# dual_vca_pnl.net
KiCad netlist of a schematic drawn in EAGLE
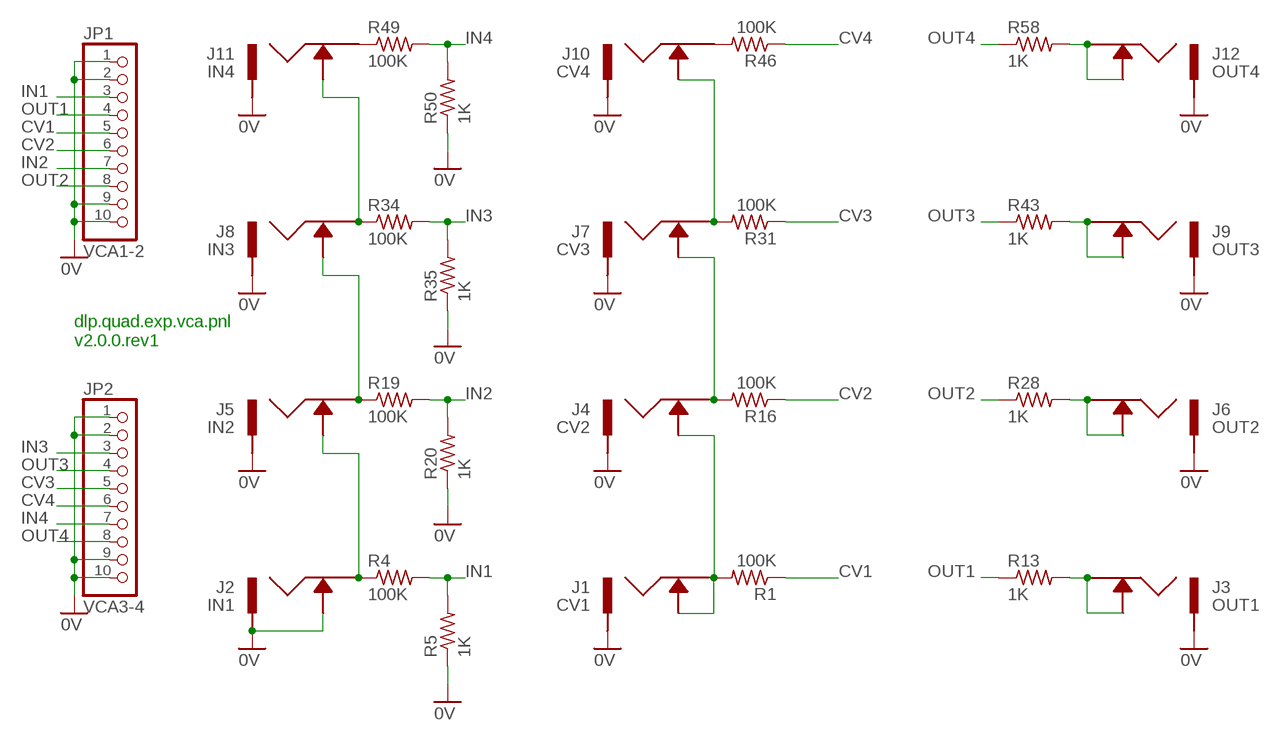
[diagram p0: schematic, sheet 1]

(export (version "E")
  (design (tool "Eeschema 10.0.6"))
  (components
    (comp (ref "J1")
      (value "CV1")
      (footprint "eagle-import:ACJM-MV35-2S")
      (libsource (lib "eagle-import") (part "ACJM-MV35-2S"))
    )
    (comp (ref "J2")
      (value "IN1")
      (footprint "eagle-import:ACJM-MV35-2S")
      (libsource (lib "eagle-import") (part "ACJM-MV35-2S"))
    )
    (comp (ref "J3")
      (value "OUT1")
      (footprint "eagle-import:ACJM-MV35-2S")
      (libsource (lib "eagle-import") (part "ACJM-MV35-2S"))
    )
    (comp (ref "J4")
      (value "CV2")
      (footprint "eagle-import:ACJM-MV35-2S")
      (libsource (lib "eagle-import") (part "ACJM-MV35-2S"))
    )
    (comp (ref "J5")
      (value "IN2")
      (footprint "eagle-import:ACJM-MV35-2S")
      (libsource (lib "eagle-import") (part "ACJM-MV35-2S"))
    )
    (comp (ref "J6")
      (value "OUT2")
      (footprint "eagle-import:ACJM-MV35-2S")
      (libsource (lib "eagle-import") (part "ACJM-MV35-2S"))
    )
    (comp (ref "J7")
      (value "CV3")
      (footprint "eagle-import:ACJM-MV35-2S")
      (libsource (lib "eagle-import") (part "ACJM-MV35-2S"))
    )
    (comp (ref "J8")
      (value "IN3")
      (footprint "eagle-import:ACJM-MV35-2S")
      (libsource (lib "eagle-import") (part "ACJM-MV35-2S"))
    )
    (comp (ref "J9")
      (value "OUT3")
      (footprint "eagle-import:ACJM-MV35-2S")
      (libsource (lib "eagle-import") (part "ACJM-MV35-2S"))
    )
    (comp (ref "J10")
      (value "CV4")
      (footprint "eagle-import:ACJM-MV35-2S")
      (libsource (lib "eagle-import") (part "ACJM-MV35-2S"))
    )
    (comp (ref "J11")
      (value "IN4")
      (footprint "eagle-import:ACJM-MV35-2S")
      (libsource (lib "eagle-import") (part "ACJM-MV35-2S"))
    )
    (comp (ref "J12")
      (value "OUT4")
      (footprint "eagle-import:ACJM-MV35-2S")
      (libsource (lib "eagle-import") (part "ACJM-MV35-2S"))
    )
    (comp (ref "JP1")
      (value "VCA1-2")
      (footprint "eagle-import:1X10")
      (libsource (lib "eagle-import") (part "PINHD-1X10"))
    )
    (comp (ref "JP2")
      (value "VCA3-4")
      (footprint "eagle-import:1X10")
      (libsource (lib "eagle-import") (part "PINHD-1X10"))
    )
    (comp (ref "R1")
      (value "100K")
      (footprint "eagle-import:0207_7")
      (libsource (lib "eagle-import") (part "R-US_0207/7"))
    )
    (comp (ref "R4")
      (value "100K")
      (footprint "eagle-import:0207_7")
      (libsource (lib "eagle-import") (part "R-US_0207/7"))
    )
    (comp (ref "R5")
      (value "1K")
      (footprint "eagle-import:0207_7")
      (libsource (lib "eagle-import") (part "R-US_0207/7"))
    )
    (comp (ref "R13")
      (value "1K")
      (footprint "eagle-import:0207_7")
      (libsource (lib "eagle-import") (part "R-US_0207/7"))
    )
    (comp (ref "R16")
      (value "100K")
      (footprint "eagle-import:0207_7")
      (libsource (lib "eagle-import") (part "R-US_0207/7"))
    )
    (comp (ref "R19")
      (value "100K")
      (footprint "eagle-import:0207_7")
      (libsource (lib "eagle-import") (part "R-US_0207/7"))
    )
    (comp (ref "R20")
      (value "1K")
      (footprint "eagle-import:0207_7")
      (libsource (lib "eagle-import") (part "R-US_0207/7"))
    )
    (comp (ref "R28")
      (value "1K")
      (footprint "eagle-import:0207_7")
      (libsource (lib "eagle-import") (part "R-US_0207/7"))
    )
    (comp (ref "R31")
      (value "100K")
      (footprint "eagle-import:0207_7")
      (libsource (lib "eagle-import") (part "R-US_0207/7"))
    )
    (comp (ref "R34")
      (value "100K")
      (footprint "eagle-import:0207_7")
      (libsource (lib "eagle-import") (part "R-US_0207/7"))
    )
    (comp (ref "R35")
      (value "1K")
      (footprint "eagle-import:0207_7")
      (libsource (lib "eagle-import") (part "R-US_0207/7"))
    )
    (comp (ref "R43")
      (value "1K")
      (footprint "eagle-import:0207_7")
      (libsource (lib "eagle-import") (part "R-US_0207/7"))
    )
    (comp (ref "R46")
      (value "100K")
      (footprint "eagle-import:0207_7")
      (libsource (lib "eagle-import") (part "R-US_0207/7"))
    )
    (comp (ref "R49")
      (value "100K")
      (footprint "eagle-import:0207_7")
      (libsource (lib "eagle-import") (part "R-US_0207/7"))
    )
    (comp (ref "R50")
      (value "1K")
      (footprint "eagle-import:0207_7")
      (libsource (lib "eagle-import") (part "R-US_0207/7"))
    )
    (comp (ref "R58")
      (value "1K")
      (footprint "eagle-import:0207_7")
      (libsource (lib "eagle-import") (part "R-US_0207/7"))
    )
  )
  (nets
    (net (code "1") (name "/CV1") (class "Default")
      (node (ref "JP1") (pin "5") (pinfunction "5_5") (pintype "passive"))
      (node (ref "R1") (pin "1") (pinfunction "1_1") (pintype "passive"))
    )
    (net (code "2") (name "/CV2") (class "Default")
      (node (ref "JP1") (pin "6") (pinfunction "6_6") (pintype "passive"))
      (node (ref "R16") (pin "1") (pinfunction "1_1") (pintype "passive"))
    )
    (net (code "3") (name "/CV3") (class "Default")
      (node (ref "JP2") (pin "5") (pinfunction "5_5") (pintype "passive"))
      (node (ref "R31") (pin "1") (pinfunction "1_1") (pintype "passive"))
    )
    (net (code "4") (name "/CV4") (class "Default")
      (node (ref "JP2") (pin "6") (pinfunction "6_6") (pintype "passive"))
      (node (ref "R46") (pin "1") (pinfunction "1_1") (pintype "passive"))
    )
    (net (code "5") (name "/IN1") (class "Default")
      (node (ref "JP1") (pin "3") (pinfunction "3_3") (pintype "passive"))
      (node (ref "R4") (pin "2") (pinfunction "2_2") (pintype "passive"))
      (node (ref "R5") (pin "2") (pinfunction "2_2") (pintype "passive"))
    )
    (net (code "6") (name "/IN2") (class "Default")
      (node (ref "JP1") (pin "7") (pinfunction "7_7") (pintype "passive"))
      (node (ref "R19") (pin "2") (pinfunction "2_2") (pintype "passive"))
      (node (ref "R20") (pin "2") (pinfunction "2_2") (pintype "passive"))
    )
    (net (code "7") (name "/IN3") (class "Default")
      (node (ref "JP2") (pin "3") (pinfunction "3_3") (pintype "passive"))
      (node (ref "R34") (pin "2") (pinfunction "2_2") (pintype "passive"))
      (node (ref "R35") (pin "2") (pinfunction "2_2") (pintype "passive"))
    )
    (net (code "8") (name "/IN4") (class "Default")
      (node (ref "JP2") (pin "7") (pinfunction "7_7") (pintype "passive"))
      (node (ref "R49") (pin "2") (pinfunction "2_2") (pintype "passive"))
      (node (ref "R50") (pin "2") (pinfunction "2_2") (pintype "passive"))
    )
    (net (code "9") (name "/OUT1") (class "Default")
      (node (ref "JP1") (pin "4") (pinfunction "4_4") (pintype "passive"))
      (node (ref "R13") (pin "1") (pinfunction "1_1") (pintype "passive"))
    )
    (net (code "10") (name "/OUT2") (class "Default")
      (node (ref "JP1") (pin "8") (pinfunction "8_8") (pintype "passive"))
      (node (ref "R28") (pin "1") (pinfunction "1_1") (pintype "passive"))
    )
    (net (code "11") (name "/OUT3") (class "Default")
      (node (ref "JP2") (pin "4") (pinfunction "4_4") (pintype "passive"))
      (node (ref "R43") (pin "1") (pinfunction "1_1") (pintype "passive"))
    )
    (net (code "12") (name "/OUT4") (class "Default")
      (node (ref "JP2") (pin "8") (pinfunction "8_8") (pintype "passive"))
      (node (ref "R58") (pin "1") (pinfunction "1_1") (pintype "passive"))
    )
    (net (code "13") (name "0V") (class "Default")
      (node (ref "J1") (pin "P$1") (pinfunction "P$1_P$1") (pintype "bidirectional"))
      (node (ref "J10") (pin "P$1") (pinfunction "P$1_P$1") (pintype "bidirectional"))
      (node (ref "J11") (pin "P$1") (pinfunction "P$1_P$1") (pintype "bidirectional"))
      (node (ref "J12") (pin "P$1") (pinfunction "P$1_P$1") (pintype "bidirectional"))
      (node (ref "J2") (pin "P$1") (pinfunction "P$1_P$1") (pintype "bidirectional"))
      (node (ref "J2") (pin "P$2") (pinfunction "P$3_P$2") (pintype "bidirectional"))
      (node (ref "J3") (pin "P$1") (pinfunction "P$1_P$1") (pintype "bidirectional"))
      (node (ref "J4") (pin "P$1") (pinfunction "P$1_P$1") (pintype "bidirectional"))
      (node (ref "J5") (pin "P$1") (pinfunction "P$1_P$1") (pintype "bidirectional"))
      (node (ref "J6") (pin "P$1") (pinfunction "P$1_P$1") (pintype "bidirectional"))
      (node (ref "J7") (pin "P$1") (pinfunction "P$1_P$1") (pintype "bidirectional"))
      (node (ref "J8") (pin "P$1") (pinfunction "P$1_P$1") (pintype "bidirectional"))
      (node (ref "J9") (pin "P$1") (pinfunction "P$1_P$1") (pintype "bidirectional"))
      (node (ref "JP1") (pin "1") (pinfunction "1_1") (pintype "passive"))
      (node (ref "JP1") (pin "10") (pinfunction "10_10") (pintype "passive"))
      (node (ref "JP1") (pin "2") (pinfunction "2_2") (pintype "passive"))
      (node (ref "JP1") (pin "9") (pinfunction "9_9") (pintype "passive"))
      (node (ref "JP2") (pin "1") (pinfunction "1_1") (pintype "passive"))
      (node (ref "JP2") (pin "10") (pinfunction "10_10") (pintype "passive"))
      (node (ref "JP2") (pin "2") (pinfunction "2_2") (pintype "passive"))
      (node (ref "JP2") (pin "9") (pinfunction "9_9") (pintype "passive"))
      (node (ref "R20") (pin "1") (pinfunction "1_1") (pintype "passive"))
      (node (ref "R35") (pin "1") (pinfunction "1_1") (pintype "passive"))
      (node (ref "R5") (pin "1") (pinfunction "1_1") (pintype "passive"))
      (node (ref "R50") (pin "1") (pinfunction "1_1") (pintype "passive"))
    )
    (net (code "14") (name "Net-(J1-P$2)") (class "Default")
      (node (ref "J1") (pin "P$2") (pinfunction "P$3_P$2") (pintype "bidirectional"))
      (node (ref "J1") (pin "P$3") (pinfunction "P$2_P$3") (pintype "bidirectional"))
      (node (ref "J4") (pin "P$2") (pinfunction "P$3_P$2") (pintype "bidirectional"))
      (node (ref "R1") (pin "2") (pinfunction "2_2") (pintype "passive"))
    )
    (net (code "15") (name "Net-(J2-P$2)") (class "Default")
      (node (ref "J2") (pin "P$3") (pinfunction "P$2_P$3") (pintype "bidirectional"))
      (node (ref "J5") (pin "P$2") (pinfunction "P$3_P$2") (pintype "bidirectional"))
      (node (ref "R4") (pin "1") (pinfunction "1_1") (pintype "passive"))
    )
    (net (code "16") (name "Net-(J3-P$2)") (class "Default")
      (node (ref "J3") (pin "P$2") (pinfunction "P$3_P$2") (pintype "bidirectional"))
      (node (ref "J3") (pin "P$3") (pinfunction "P$2_P$3") (pintype "bidirectional"))
      (node (ref "R13") (pin "2") (pinfunction "2_2") (pintype "passive"))
    )
    (net (code "17") (name "Net-(J4-P$2)") (class "Default")
      (node (ref "J4") (pin "P$3") (pinfunction "P$2_P$3") (pintype "bidirectional"))
      (node (ref "J7") (pin "P$2") (pinfunction "P$3_P$2") (pintype "bidirectional"))
      (node (ref "R16") (pin "2") (pinfunction "2_2") (pintype "passive"))
    )
    (net (code "18") (name "Net-(J5-P$2)") (class "Default")
      (node (ref "J5") (pin "P$3") (pinfunction "P$2_P$3") (pintype "bidirectional"))
      (node (ref "J8") (pin "P$2") (pinfunction "P$3_P$2") (pintype "bidirectional"))
      (node (ref "R19") (pin "1") (pinfunction "1_1") (pintype "passive"))
    )
    (net (code "19") (name "Net-(J6-P$2)") (class "Default")
      (node (ref "J6") (pin "P$2") (pinfunction "P$3_P$2") (pintype "bidirectional"))
      (node (ref "J6") (pin "P$3") (pinfunction "P$2_P$3") (pintype "bidirectional"))
      (node (ref "R28") (pin "2") (pinfunction "2_2") (pintype "passive"))
    )
    (net (code "20") (name "Net-(J9-P$2)") (class "Default")
      (node (ref "J9") (pin "P$2") (pinfunction "P$3_P$2") (pintype "bidirectional"))
      (node (ref "J9") (pin "P$3") (pinfunction "P$2_P$3") (pintype "bidirectional"))
      (node (ref "R43") (pin "2") (pinfunction "2_2") (pintype "passive"))
    )
    (net (code "21") (name "Net-(J10-P$2)") (class "Default")
      (node (ref "J10") (pin "P$3") (pinfunction "P$2_P$3") (pintype "bidirectional"))
      (node (ref "R46") (pin "2") (pinfunction "2_2") (pintype "passive"))
    )
    (net (code "22") (name "Net-(J10-P$3)") (class "Default")
      (node (ref "J10") (pin "P$2") (pinfunction "P$3_P$2") (pintype "bidirectional"))
      (node (ref "J7") (pin "P$3") (pinfunction "P$2_P$3") (pintype "bidirectional"))
      (node (ref "R31") (pin "2") (pinfunction "2_2") (pintype "passive"))
    )
    (net (code "23") (name "Net-(J11-P$2)") (class "Default")
      (node (ref "J11") (pin "P$3") (pinfunction "P$2_P$3") (pintype "bidirectional"))
      (node (ref "R49") (pin "1") (pinfunction "1_1") (pintype "passive"))
    )
    (net (code "24") (name "Net-(J11-P$3)") (class "Default")
      (node (ref "J11") (pin "P$2") (pinfunction "P$3_P$2") (pintype "bidirectional"))
      (node (ref "J8") (pin "P$3") (pinfunction "P$2_P$3") (pintype "bidirectional"))
      (node (ref "R34") (pin "1") (pinfunction "1_1") (pintype "passive"))
    )
    (net (code "25") (name "Net-(J12-P$2)") (class "Default")
      (node (ref "J12") (pin "P$2") (pinfunction "P$3_P$2") (pintype "bidirectional"))
      (node (ref "J12") (pin "P$3") (pinfunction "P$2_P$3") (pintype "bidirectional"))
      (node (ref "R58") (pin "2") (pinfunction "2_2") (pintype "passive"))
    )
  )
)
